# TUSB8041_Power_Logic_2.net
KiCad netlist of a schematic drawn in Altium Designer
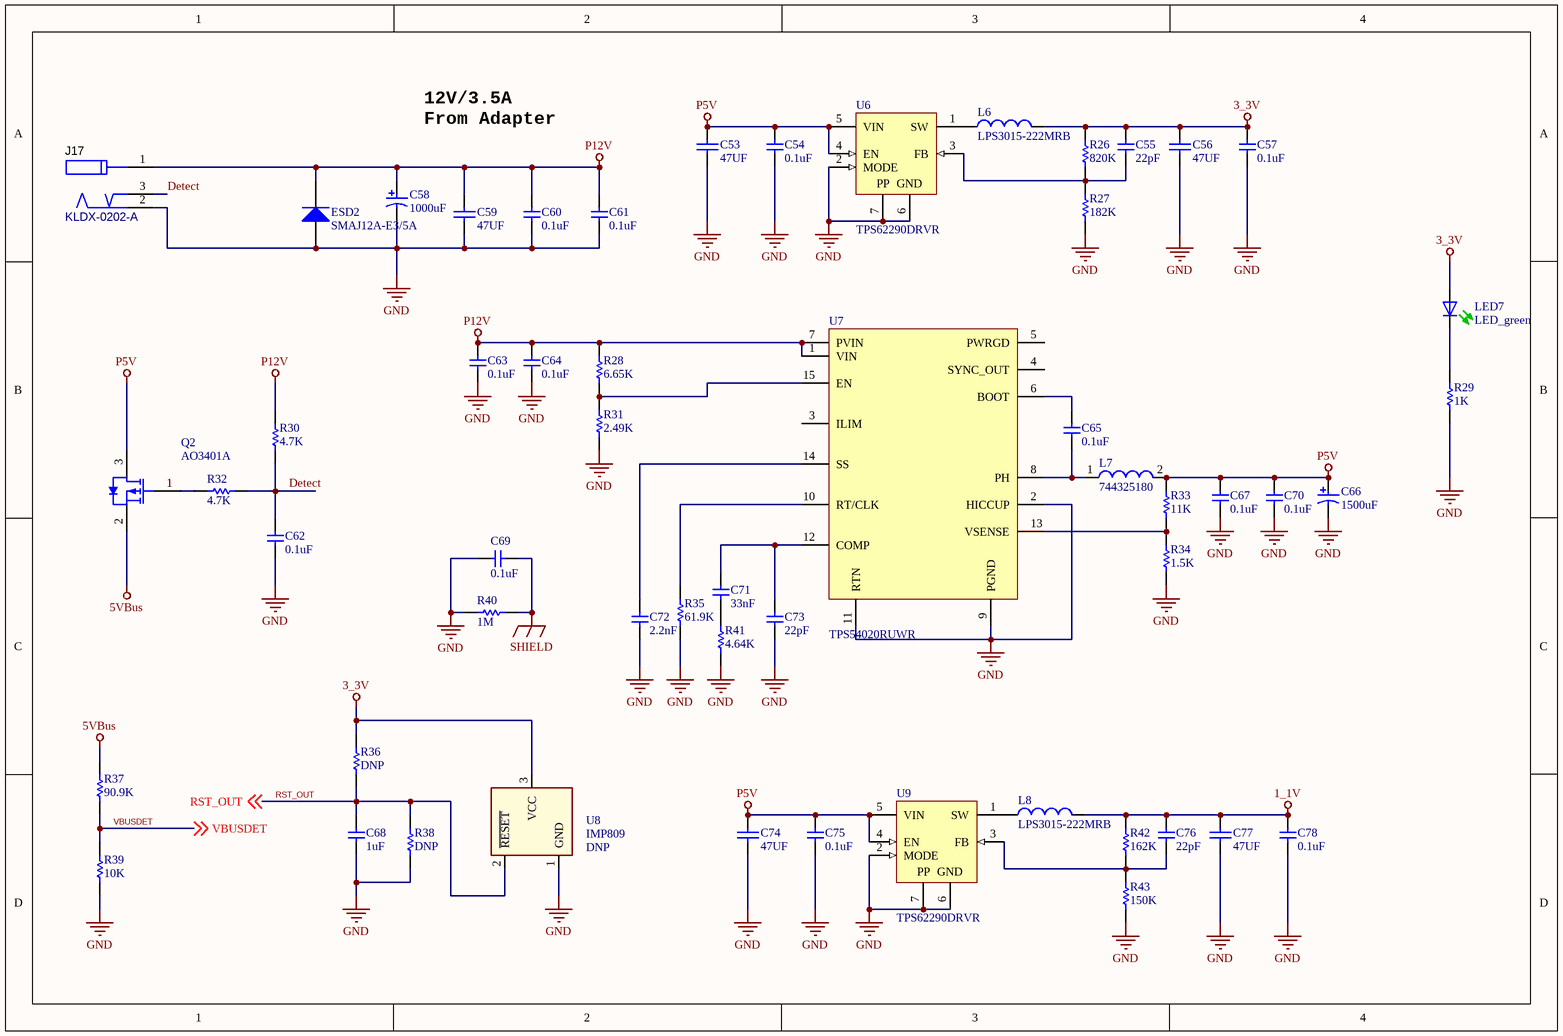
[diagram p0: TUSB8041_Power_Logic_2.SchDoc]

(export (version "E")
  (design (tool "Eeschema 10.0.6"))
  (components
    (comp (ref "C53")
      (value "47UF")
      (footprint "CAPC1210(3225)200_L")
      (description "1210 (3225 Metric) Chip Capacitor")
      (libsource (lib "IC0") (part "CAP_5_2"))
    )
    (comp (ref "C54")
      (value "0.1uF")
      (footprint "CAP0603")
      (description "Capacitor")
      (fields (field (name "PUBLISHER") "Altium Limited"))
      (libsource (lib "TUSB8041_USB_3.0_Hub") (part "CAP"))
    )
    (comp (ref "C55")
      (value "22pF")
      (footprint "CAP0603")
      (description "Capacitor")
      (fields (field (name "PUBLISHER") "Altium Limited"))
      (libsource (lib "TUSB8041_USB_3.0_Hub") (part "CAP"))
    )
    (comp (ref "C56")
      (value "47UF")
      (footprint "CAPC1210(3225)200_L")
      (description "1210 (3225 Metric) Chip Capacitor")
      (libsource (lib "IC0") (part "CAP_5_2"))
    )
    (comp (ref "C57")
      (value "0.1uF")
      (footprint "CAP0603")
      (description "Capacitor")
      (fields (field (name "PUBLISHER") "Altium Limited"))
      (libsource (lib "TUSB8041_USB_3.0_Hub") (part "CAP"))
    )
    (comp (ref "C58")
      (value "1000uF")
      (footprint "NIC-UVR-10x12.5-2_V")
      (description "Aluminum Electrolytic Capacitor, 63 V, -40 to 85 degC, 2-Pin CAP, RoHS")
      (fields (field (name "MANUFACTURER") "Nichicon") (field (name "PARTNUMBER") "UVR1J101MPD1TD"))
      (libsource (lib "Altium Content Vault") (part "NIC-CAP-P-2"))
    )
    (comp (ref "C59")
      (value "47UF")
      (footprint "CAPC1210(3225)200_L")
      (description "1210 (3225 Metric) Chip Capacitor")
      (libsource (lib "IC0") (part "CAP_5_2"))
    )
    (comp (ref "C60")
      (value "0.1uF")
      (footprint "CAP0603")
      (description "Capacitor")
      (fields (field (name "PUBLISHER") "Altium Limited"))
      (libsource (lib "TUSB8041_USB_3.0_Hub") (part "CAP"))
    )
    (comp (ref "C61")
      (value "0.1uF")
      (footprint "CAP0603")
      (description "Capacitor")
      (fields (field (name "PUBLISHER") "Altium Limited"))
      (libsource (lib "TUSB8041_USB_3.0_Hub") (part "CAP"))
    )
    (comp (ref "C62")
      (value "0.1uF")
      (footprint "CAP0603")
      (description "Capacitor")
      (fields (field (name "PUBLISHER") "Altium Limited"))
      (libsource (lib "TUSB8041_USB_3.0_Hub") (part "CAP"))
    )
    (comp (ref "C63")
      (value "0.1uF")
      (footprint "CAP0805")
      (description "Capacitor")
      (fields (field (name "PUBLISHER") "Altium Limited"))
      (libsource (lib "TUSB8041_USB_3.0_Hub") (part "CAP"))
    )
    (comp (ref "C64")
      (value "0.1uF")
      (footprint "CAP0603")
      (description "Capacitor")
      (fields (field (name "PUBLISHER") "Altium Limited"))
      (libsource (lib "TUSB8041_USB_3.0_Hub") (part "CAP"))
    )
    (comp (ref "C65")
      (value "0.1uF")
      (footprint "CAP0603")
      (description "Capacitor")
      (fields (field (name "PUBLISHER") "Altium Limited"))
      (libsource (lib "TUSB8041_USB_3.0_Hub") (part "CAP"))
    )
    (comp (ref "C66")
      (value "1500uF")
      (footprint "NIC-UVR-10x12.5-2_V")
      (description "Aluminum Electrolytic Capacitor, 6.3 V, -40 to 85 degC, 2-Pin CAP, RoHS")
      (fields (field (name "MANUFACTURER") "Nichicon") (field (name "PARTNUMBER") "UVR1J101MPD1TD"))
      (libsource (lib "Altium Content Vault") (part "NIC-CAP-P-2"))
    )
    (comp (ref "C67")
      (value "0.1uF")
      (footprint "CAP0805")
      (description "Capacitor")
      (fields (field (name "PUBLISHER") "Altium Limited"))
      (libsource (lib "TUSB8041_USB_3.0_Hub") (part "CAP"))
    )
    (comp (ref "C68")
      (value "1uF")
      (footprint "CAP0603")
      (description "Capacitor")
      (fields (field (name "PUBLISHER") "Altium Limited"))
      (libsource (lib "TUSB8041_USB_3.0_Hub") (part "CAP"))
    )
    (comp (ref "C69")
      (value "0.1uF")
      (footprint "CAP0603")
      (description "Capacitor")
      (fields (field (name "PUBLISHER") "Altium Limited"))
      (libsource (lib "TUSB8041_USB_3.0_Hub") (part "CAP"))
    )
    (comp (ref "C70")
      (value "0.1uF")
      (footprint "CAP0603")
      (description "Capacitor")
      (fields (field (name "PUBLISHER") "Altium Limited"))
      (libsource (lib "TUSB8041_USB_3.0_Hub") (part "CAP"))
    )
    (comp (ref "C71")
      (value "33nF")
      (footprint "CAP0603")
      (description "Capacitor")
      (fields (field (name "PUBLISHER") "Altium Limited"))
      (libsource (lib "TUSB8041_USB_3.0_Hub") (part "CAP"))
    )
    (comp (ref "C72")
      (value "2.2nF")
      (footprint "CAP0603")
      (description "Capacitor")
      (fields (field (name "PUBLISHER") "Altium Limited"))
      (libsource (lib "TUSB8041_USB_3.0_Hub") (part "CAP"))
    )
    (comp (ref "C73")
      (value "22pF")
      (footprint "CAP0603")
      (description "Capacitor")
      (fields (field (name "PUBLISHER") "Altium Limited"))
      (libsource (lib "TUSB8041_USB_3.0_Hub") (part "CAP"))
    )
    (comp (ref "C74")
      (value "47UF")
      (footprint "CAPC1210(3225)200_L")
      (description "1210 (3225 Metric) Chip Capacitor")
      (libsource (lib "IC0") (part "CAP_5_2"))
    )
    (comp (ref "C75")
      (value "0.1uF")
      (footprint "CAP0603")
      (description "Capacitor")
      (fields (field (name "PUBLISHER") "Altium Limited"))
      (libsource (lib "TUSB8041_USB_3.0_Hub") (part "CAP"))
    )
    (comp (ref "C76")
      (value "22pF")
      (footprint "CAP0603")
      (description "Capacitor")
      (fields (field (name "PUBLISHER") "Altium Limited"))
      (libsource (lib "TUSB8041_USB_3.0_Hub") (part "CAP"))
    )
    (comp (ref "C77")
      (value "47UF")
      (footprint "CAPC1210(3225)200_L")
      (description "1210 (3225 Metric) Chip Capacitor")
      (libsource (lib "IC0") (part "CAP_5_2"))
    )
    (comp (ref "C78")
      (value "0.1uF")
      (footprint "CAP0603")
      (description "Capacitor")
      (fields (field (name "PUBLISHER") "Altium Limited"))
      (libsource (lib "TUSB8041_USB_3.0_Hub") (part "CAP"))
    )
    (comp (ref "ESD2")
      (value "SMAJ12A-E3/5A")
      (footprint "VISH-DO-214AC-2_M")
      (fields (field (name "MANUFACTURER") "Vishay Semiconductor"))
      (libsource (lib "Altium Content Vault") (part "VISH-K1A2-2"))
    )
    (comp (ref "J17")
      (value "KLDX-0202-A")
      (footprint "KYCN-KLDX-0202-A_V")
      (description "DC Power Connectors 2mm PCB JACK POWER JACK")
      (libsource (lib "Altium Content Vault") (part "CONN_DC JACK"))
    )
    (comp (ref "L6")
      (value "LPS3015-222MRB")
      (footprint "COIL-LPS3015_V")
      (description "Shielded Power Inductor, 2.2 uH, +/- 20%, 110 mOhm, -40 to 85 degC, 2-Pin SMD, RoHS, Tape and Reel")
      (fields (field (name "MANUFACTURER") "Coilcraft") (field (name "TOLERANCE") "20%"))
      (libsource (lib "Altium Content Vault") (part "IND-2"))
    )
    (comp (ref "L7")
      (value "744325180")
      (footprint "WE-HCI-1050")
      (description "SMD Flat Wire High Current Inductor WE-HCI, L=1.80 µH")
      (libsource (lib "Altium Content Vault") (part "PAS-IND-INDUCTOR-2"))
    )
    (comp (ref "L8")
      (value "LPS3015-222MRB")
      (footprint "COIL-LPS3015_V")
      (description "Shielded Power Inductor, 2.2 uH, +/- 20%, 110 mOhm, -40 to 85 degC, 2-Pin SMD, RoHS, Tape and Reel")
      (fields (field (name "MANUFACTURER") "Coilcraft") (field (name "TOLERANCE") "20%"))
      (libsource (lib "Altium Content Vault") (part "IND-2"))
    )
    (comp (ref "LED7")
      (value "LED_green")
      (footprint "LED-0603-GREEN")
      (libsource (lib "TUSB8041_USB_3.0_Hub") (part "LED_green"))
    )
    (comp (ref "Q2")
      (value "AO3401A")
      (footprint "AO-SOT-23-3L_V")
      (description "P-Channel MOSFET, 30 V, 4 A, -55 to 150 degC, 3-Pin SOT-23-3L, RoHS, Tape and Reel")
      (fields (field (name "MANUFACTURER") "Alpha and Omega"))
      (libsource (lib "Altium Content Vault") (part "PEMOS-GSD-3"))
    )
    (comp (ref "R26")
      (value "820K")
      (footprint "RES0603")
      (description "Resistor")
      (fields (field (name "PUBLISHER") "Altium Limited"))
      (libsource (lib "VL812_USB_3.0_Hub") (part "RES"))
    )
    (comp (ref "R27")
      (value "182K")
      (footprint "RES0603")
      (description "Resistor")
      (fields (field (name "PUBLISHER") "Altium Limited"))
      (libsource (lib "VL812_USB_3.0_Hub") (part "RES"))
    )
    (comp (ref "R28")
      (value "6.65K")
      (footprint "RES0603")
      (description "Resistor")
      (fields (field (name "PUBLISHER") "Altium Limited"))
      (libsource (lib "VL812_USB_3.0_Hub") (part "RES"))
    )
    (comp (ref "R29")
      (value "1K")
      (footprint "RES0603")
      (description "Resistor")
      (fields (field (name "PUBLISHER") "Altium Limited"))
      (libsource (lib "TUSB8041_USB_3.0_Hub") (part "RES"))
    )
    (comp (ref "R30")
      (value "4.7K")
      (footprint "RES0603")
      (description "Resistor")
      (fields (field (name "PUBLISHER") "Altium Limited"))
      (libsource (lib "VL812_USB_3.0_Hub") (part "RES"))
    )
    (comp (ref "R31")
      (value "2.49K")
      (footprint "RES0603")
      (description "Resistor")
      (fields (field (name "PUBLISHER") "Altium Limited"))
      (libsource (lib "VL812_USB_3.0_Hub") (part "RES"))
    )
    (comp (ref "R32")
      (value "4.7K")
      (footprint "RES0603")
      (description "Resistor")
      (fields (field (name "PUBLISHER") "Altium Limited"))
      (libsource (lib "VL812_USB_3.0_Hub") (part "RES"))
    )
    (comp (ref "R33")
      (value "11K")
      (footprint "RES0603")
      (description "Resistor")
      (fields (field (name "PUBLISHER") "Altium Limited"))
      (libsource (lib "VL812_USB_3.0_Hub") (part "RES"))
    )
    (comp (ref "R34")
      (value "1.5K")
      (footprint "RES0603")
      (description "Resistor")
      (fields (field (name "PUBLISHER") "Altium Limited"))
      (libsource (lib "VL812_USB_3.0_Hub") (part "RES"))
    )
    (comp (ref "R35")
      (value "61.9K")
      (footprint "RES0603")
      (description "Resistor")
      (fields (field (name "PUBLISHER") "Altium Limited"))
      (libsource (lib "VL812_USB_3.0_Hub") (part "RES"))
    )
    (comp (ref "R36")
      (value "DNP")
      (footprint "RES0603")
      (description "Resistor")
      (fields (field (name "PUBLISHER") "Altium Limited"))
      (libsource (lib "VL812_USB_3.0_Hub") (part "RES"))
    )
    (comp (ref "R37")
      (value "90.9K")
      (footprint "RES0603")
      (description "Resistor")
      (fields (field (name "PUBLISHER") "Altium Limited"))
      (libsource (lib "VL812_USB_3.0_Hub") (part "RES"))
    )
    (comp (ref "R38")
      (value "DNP")
      (footprint "RES0603")
      (description "Resistor")
      (fields (field (name "PUBLISHER") "Altium Limited"))
      (libsource (lib "VL812_USB_3.0_Hub") (part "RES"))
    )
    (comp (ref "R39")
      (value "10K")
      (footprint "RES0603")
      (description "Resistor")
      (fields (field (name "PUBLISHER") "Altium Limited"))
      (libsource (lib "VL812_USB_3.0_Hub") (part "RES"))
    )
    (comp (ref "R40")
      (value "1M")
      (footprint "RES0805")
      (description "Resistor")
      (fields (field (name "PUBLISHER") "Altium Limited"))
      (libsource (lib "TUSB8041_USB_3.0_Hub") (part "RES"))
    )
    (comp (ref "R41")
      (value "4.64K")
      (footprint "RES0603")
      (description "Resistor")
      (fields (field (name "PUBLISHER") "Altium Limited"))
      (libsource (lib "VL812_USB_3.0_Hub") (part "RES"))
    )
    (comp (ref "R42")
      (value "162K")
      (footprint "RES0603")
      (description "Resistor")
      (fields (field (name "PUBLISHER") "Altium Limited"))
      (libsource (lib "VL812_USB_3.0_Hub") (part "RES"))
    )
    (comp (ref "R43")
      (value "150K")
      (footprint "RES0603")
      (description "Resistor")
      (fields (field (name "PUBLISHER") "Altium Limited"))
      (libsource (lib "VL812_USB_3.0_Hub") (part "RES"))
    )
    (comp (ref "U6")
      (value "TPS62290DRVR")
      (footprint "DRV6-1600X1000TP")
      (fields (field (name "MANUFACTURER") "Texas Instruments"))
      (libsource (lib "Altium Content Vault") (part "TI-TPS62290DRV6-1600X1000TP"))
    )
    (comp (ref "U7")
      (value "TPS54020RUWR")
      (footprint "R-PVQFN-N15")
      (fields (field (name "PACKAGEREFERENCE") "TPS54020RUWR"))
      (libsource (lib "TUSB8041_USB_3.0_Hub") (part "TPS54020RUWR"))
    )
    (comp (ref "U8")
      (value "IMP809")
      (footprint "SOT23")
      (description "Power Monitor")
      (fields (field (name "PARAMETER 1") "DNP"))
      (libsource (lib "TUSB8041_USB_3.0_Hub") (part "IMP809"))
    )
    (comp (ref "U9")
      (value "TPS62290DRVR")
      (footprint "DRV6-1600X1000TP")
      (fields (field (name "MANUFACTURER") "Texas Instruments"))
      (libsource (lib "Altium Content Vault") (part "TI-TPS62290DRV6-1600X1000TP"))
    )
  )
  (nets
    (net (code "1") (name "/Detect") (class "Default")
      (node (ref "C62") (pin "2") (pinfunction "2_2") (pintype "passive"))
      (node (ref "J17") (pin "3") (pinfunction "3_3") (pintype "passive"))
      (node (ref "R30") (pin "2") (pinfunction "2_2") (pintype "passive"))
      (node (ref "R32") (pin "2") (pinfunction "2_2") (pintype "passive"))
    )
    (net (code "2") (name "1_1V") (class "Default")
      (node (ref "C76") (pin "2") (pinfunction "2_2") (pintype "passive"))
      (node (ref "C77") (pin "2") (pinfunction "2_2") (pintype "passive"))
      (node (ref "C78") (pin "2") (pinfunction "2_2") (pintype "passive"))
      (node (ref "L8") (pin "2") (pinfunction "2_2") (pintype "passive"))
      (node (ref "R42") (pin "1") (pinfunction "1_1") (pintype "passive"))
    )
    (net (code "3") (name "3_3V") (class "Default")
      (node (ref "C55") (pin "2") (pinfunction "2_2") (pintype "passive"))
      (node (ref "C56") (pin "2") (pinfunction "2_2") (pintype "passive"))
      (node (ref "C57") (pin "2") (pinfunction "2_2") (pintype "passive"))
      (node (ref "L6") (pin "2") (pinfunction "2_2") (pintype "passive"))
      (node (ref "LED7") (pin "A") (pinfunction "A_A") (pintype "power_in"))
      (node (ref "R26") (pin "1") (pinfunction "1_1") (pintype "passive"))
      (node (ref "R36") (pin "1") (pinfunction "1_1") (pintype "passive"))
      (node (ref "U8") (pin "3") (pinfunction "VCC_3") (pintype "passive"))
    )
    (net (code "4") (name "5VBus") (class "Default")
      (node (ref "Q2") (pin "2") (pinfunction "SOURCE_2") (pintype "passive"))
      (node (ref "R37") (pin "1") (pinfunction "1_1") (pintype "passive"))
    )
    (net (code "5") (name "GND") (class "Default")
      (node (ref "C53") (pin "1") (pinfunction "1_1") (pintype "passive"))
      (node (ref "C54") (pin "1") (pinfunction "1_1") (pintype "passive"))
      (node (ref "C56") (pin "1") (pinfunction "1_1") (pintype "passive"))
      (node (ref "C57") (pin "1") (pinfunction "1_1") (pintype "passive"))
      (node (ref "C58") (pin "2") (pinfunction "2_2") (pintype "passive"))
      (node (ref "C59") (pin "1") (pinfunction "1_1") (pintype "passive"))
      (node (ref "C60") (pin "1") (pinfunction "1_1") (pintype "passive"))
      (node (ref "C61") (pin "1") (pinfunction "1_1") (pintype "passive"))
      (node (ref "C62") (pin "1") (pinfunction "1_1") (pintype "passive"))
      (node (ref "C63") (pin "1") (pinfunction "1_1") (pintype "passive"))
      (node (ref "C64") (pin "1") (pinfunction "1_1") (pintype "passive"))
      (node (ref "C66") (pin "2") (pinfunction "2_2") (pintype "passive"))
      (node (ref "C67") (pin "1") (pinfunction "1_1") (pintype "passive"))
      (node (ref "C68") (pin "1") (pinfunction "1_1") (pintype "passive"))
      (node (ref "C69") (pin "2") (pinfunction "2_2") (pintype "passive"))
      (node (ref "C70") (pin "1") (pinfunction "1_1") (pintype "passive"))
      (node (ref "C72") (pin "1") (pinfunction "1_1") (pintype "passive"))
      (node (ref "C73") (pin "1") (pinfunction "1_1") (pintype "passive"))
      (node (ref "C74") (pin "1") (pinfunction "1_1") (pintype "passive"))
      (node (ref "C75") (pin "1") (pinfunction "1_1") (pintype "passive"))
      (node (ref "C77") (pin "1") (pinfunction "1_1") (pintype "passive"))
      (node (ref "C78") (pin "1") (pinfunction "1_1") (pintype "passive"))
      (node (ref "ESD2") (pin "2") (pinfunction "A_2") (pintype "passive"))
      (node (ref "J17") (pin "2") (pinfunction "2_2") (pintype "passive"))
      (node (ref "R27") (pin "2") (pinfunction "2_2") (pintype "passive"))
      (node (ref "R29") (pin "1") (pinfunction "1_1") (pintype "passive"))
      (node (ref "R31") (pin "2") (pinfunction "2_2") (pintype "passive"))
      (node (ref "R34") (pin "2") (pinfunction "2_2") (pintype "passive"))
      (node (ref "R35") (pin "2") (pinfunction "2_2") (pintype "passive"))
      (node (ref "R38") (pin "2") (pinfunction "2_2") (pintype "passive"))
      (node (ref "R39") (pin "2") (pinfunction "2_2") (pintype "passive"))
      (node (ref "R40") (pin "1") (pinfunction "1_1") (pintype "passive"))
      (node (ref "R41") (pin "2") (pinfunction "2_2") (pintype "passive"))
      (node (ref "R43") (pin "2") (pinfunction "2_2") (pintype "passive"))
      (node (ref "U6") (pin "2") (pinfunction "MODE_2") (pintype "input"))
      (node (ref "U6") (pin "6") (pinfunction "GND_6") (pintype "power_in"))
      (node (ref "U6") (pin "7") (pinfunction "PP_7") (pintype "power_in"))
      (node (ref "U7") (pin "11") (pinfunction "RTN_11") (pintype "passive"))
      (node (ref "U7") (pin "2") (pinfunction "HICCUP_2") (pintype "passive"))
      (node (ref "U7") (pin "9") (pinfunction "PGND_9") (pintype "passive"))
      (node (ref "U8") (pin "1") (pinfunction "GND_1") (pintype "passive"))
      (node (ref "U9") (pin "2") (pinfunction "MODE_2") (pintype "input"))
      (node (ref "U9") (pin "6") (pinfunction "GND_6") (pintype "power_in"))
      (node (ref "U9") (pin "7") (pinfunction "PP_7") (pintype "power_in"))
    )
    (net (code "6") (name "Net-(C71-Pad1)") (class "Default")
      (node (ref "C71") (pin "1") (pinfunction "1_1") (pintype "passive"))
      (node (ref "R41") (pin "1") (pinfunction "1_1") (pintype "passive"))
    )
    (net (code "7") (name "Net-(LED7-C)") (class "Default")
      (node (ref "LED7") (pin "K") (pinfunction "C_K") (pintype "power_in"))
      (node (ref "R29") (pin "2") (pinfunction "2_2") (pintype "passive"))
    )
    (net (code "8") (name "Net-(Q2-GATE)") (class "Default")
      (node (ref "Q2") (pin "1") (pinfunction "GATE_1") (pintype "passive"))
      (node (ref "R32") (pin "1") (pinfunction "1_1") (pintype "passive"))
    )
    (net (code "9") (name "Net-(U6-FB)") (class "Default")
      (node (ref "C55") (pin "1") (pinfunction "1_1") (pintype "passive"))
      (node (ref "R26") (pin "2") (pinfunction "2_2") (pintype "passive"))
      (node (ref "R27") (pin "1") (pinfunction "1_1") (pintype "passive"))
      (node (ref "U6") (pin "3") (pinfunction "FB_3") (pintype "input"))
    )
    (net (code "10") (name "Net-(U6-SW)") (class "Default")
      (node (ref "L6") (pin "1") (pinfunction "1_1") (pintype "passive"))
      (node (ref "U6") (pin "1") (pinfunction "SW_1") (pintype "power_in"))
    )
    (net (code "11") (name "Net-(U7-BOOT)") (class "Default")
      (node (ref "C65") (pin "2") (pinfunction "2_2") (pintype "passive"))
      (node (ref "U7") (pin "6") (pinfunction "BOOT_6") (pintype "passive"))
    )
    (net (code "12") (name "Net-(U7-COMP)") (class "Default")
      (node (ref "C71") (pin "2") (pinfunction "2_2") (pintype "passive"))
      (node (ref "C73") (pin "2") (pinfunction "2_2") (pintype "passive"))
      (node (ref "U7") (pin "12") (pinfunction "COMP_12") (pintype "passive"))
    )
    (net (code "13") (name "Net-(U7-EN)") (class "Default")
      (node (ref "R28") (pin "2") (pinfunction "2_2") (pintype "passive"))
      (node (ref "R31") (pin "1") (pinfunction "1_1") (pintype "passive"))
      (node (ref "U7") (pin "15") (pinfunction "EN_15") (pintype "passive"))
    )
    (net (code "14") (name "Net-(U7-PH)") (class "Default")
      (node (ref "C65") (pin "1") (pinfunction "1_1") (pintype "passive"))
      (node (ref "L7") (pin "1") (pinfunction "1_1") (pintype "passive"))
      (node (ref "U7") (pin "8") (pinfunction "PH_8") (pintype "passive"))
    )
    (net (code "15") (name "Net-(U7-RT{slash}CLK)") (class "Default")
      (node (ref "R35") (pin "1") (pinfunction "1_1") (pintype "passive"))
      (node (ref "U7") (pin "10") (pinfunction "RT/CLK_10") (pintype "passive"))
    )
    (net (code "16") (name "Net-(U7-SS)") (class "Default")
      (node (ref "C72") (pin "2") (pinfunction "2_2") (pintype "passive"))
      (node (ref "U7") (pin "14") (pinfunction "SS_14") (pintype "passive"))
    )
    (net (code "17") (name "Net-(U7-VSENSE)") (class "Default")
      (node (ref "R33") (pin "2") (pinfunction "2_2") (pintype "passive"))
      (node (ref "R34") (pin "1") (pinfunction "1_1") (pintype "passive"))
      (node (ref "U7") (pin "13") (pinfunction "VSENSE_13") (pintype "passive"))
    )
    (net (code "18") (name "Net-(U9-FB)") (class "Default")
      (node (ref "C76") (pin "1") (pinfunction "1_1") (pintype "passive"))
      (node (ref "R42") (pin "2") (pinfunction "2_2") (pintype "passive"))
      (node (ref "R43") (pin "1") (pinfunction "1_1") (pintype "passive"))
      (node (ref "U9") (pin "3") (pinfunction "FB_3") (pintype "input"))
    )
    (net (code "19") (name "Net-(U9-SW)") (class "Default")
      (node (ref "L8") (pin "1") (pinfunction "1_1") (pintype "passive"))
      (node (ref "U9") (pin "1") (pinfunction "SW_1") (pintype "power_in"))
    )
    (net (code "20") (name "P5V") (class "Default")
      (node (ref "C53") (pin "2") (pinfunction "2_2") (pintype "passive"))
      (node (ref "C54") (pin "2") (pinfunction "2_2") (pintype "passive"))
      (node (ref "C66") (pin "1") (pinfunction "1_1") (pintype "passive"))
      (node (ref "C67") (pin "2") (pinfunction "2_2") (pintype "passive"))
      (node (ref "C70") (pin "2") (pinfunction "2_2") (pintype "passive"))
      (node (ref "C74") (pin "2") (pinfunction "2_2") (pintype "passive"))
      (node (ref "C75") (pin "2") (pinfunction "2_2") (pintype "passive"))
      (node (ref "L7") (pin "2") (pinfunction "2_2") (pintype "passive"))
      (node (ref "Q2") (pin "3") (pinfunction "DRAIN_3") (pintype "passive"))
      (node (ref "R33") (pin "1") (pinfunction "1_1") (pintype "passive"))
      (node (ref "U6") (pin "4") (pinfunction "EN_4") (pintype "input"))
      (node (ref "U6") (pin "5") (pinfunction "VIN_5") (pintype "power_in"))
      (node (ref "U9") (pin "4") (pinfunction "EN_4") (pintype "input"))
      (node (ref "U9") (pin "5") (pinfunction "VIN_5") (pintype "power_in"))
    )
    (net (code "21") (name "P12V") (class "Default")
      (node (ref "C58") (pin "1") (pinfunction "1_1") (pintype "passive"))
      (node (ref "C59") (pin "2") (pinfunction "2_2") (pintype "passive"))
      (node (ref "C60") (pin "2") (pinfunction "2_2") (pintype "passive"))
      (node (ref "C61") (pin "2") (pinfunction "2_2") (pintype "passive"))
      (node (ref "C63") (pin "2") (pinfunction "2_2") (pintype "passive"))
      (node (ref "C64") (pin "2") (pinfunction "2_2") (pintype "passive"))
      (node (ref "ESD2") (pin "1") (pinfunction "K_1") (pintype "passive"))
      (node (ref "J17") (pin "1") (pinfunction "1_1") (pintype "passive"))
      (node (ref "R28") (pin "1") (pinfunction "1_1") (pintype "passive"))
      (node (ref "R30") (pin "1") (pinfunction "1_1") (pintype "passive"))
      (node (ref "U7") (pin "1") (pinfunction "VIN_1") (pintype "passive"))
      (node (ref "U7") (pin "7") (pinfunction "PVIN_7") (pintype "passive"))
    )
    (net (code "22") (name "RST_OUT") (class "Default")
      (node (ref "C68") (pin "2") (pinfunction "2_2") (pintype "passive"))
      (node (ref "R36") (pin "2") (pinfunction "2_2") (pintype "passive"))
      (node (ref "R38") (pin "1") (pinfunction "1_1") (pintype "passive"))
      (node (ref "U8") (pin "2") (pinfunction "~{RESET}_2") (pintype "passive"))
    )
    (net (code "23") (name "SHIELD") (class "Default")
      (node (ref "C69") (pin "1") (pinfunction "1_1") (pintype "passive"))
      (node (ref "R40") (pin "2") (pinfunction "2_2") (pintype "passive"))
    )
    (net (code "24") (name "VBUSDET") (class "Default")
      (node (ref "R37") (pin "2") (pinfunction "2_2") (pintype "passive"))
      (node (ref "R39") (pin "1") (pinfunction "1_1") (pintype "passive"))
    )
    (net (code "25") (name "unconnected-(U7-ILIM-Pad3)") (class "Default")
      (node (ref "U7") (pin "3") (pinfunction "ILIM_3") (pintype "passive"))
    )
    (net (code "26") (name "unconnected-(U7-PWRGD-Pad5)") (class "Default")
      (node (ref "U7") (pin "5") (pinfunction "PWRGD_5") (pintype "passive"))
    )
    (net (code "27") (name "unconnected-(U7-SYNC_OUT-Pad4)") (class "Default")
      (node (ref "U7") (pin "4") (pinfunction "SYNC_OUT_4") (pintype "passive"))
    )
  )
)
